# ver060_MCU.net
KiCad netlist of a schematic drawn in Altium Designer
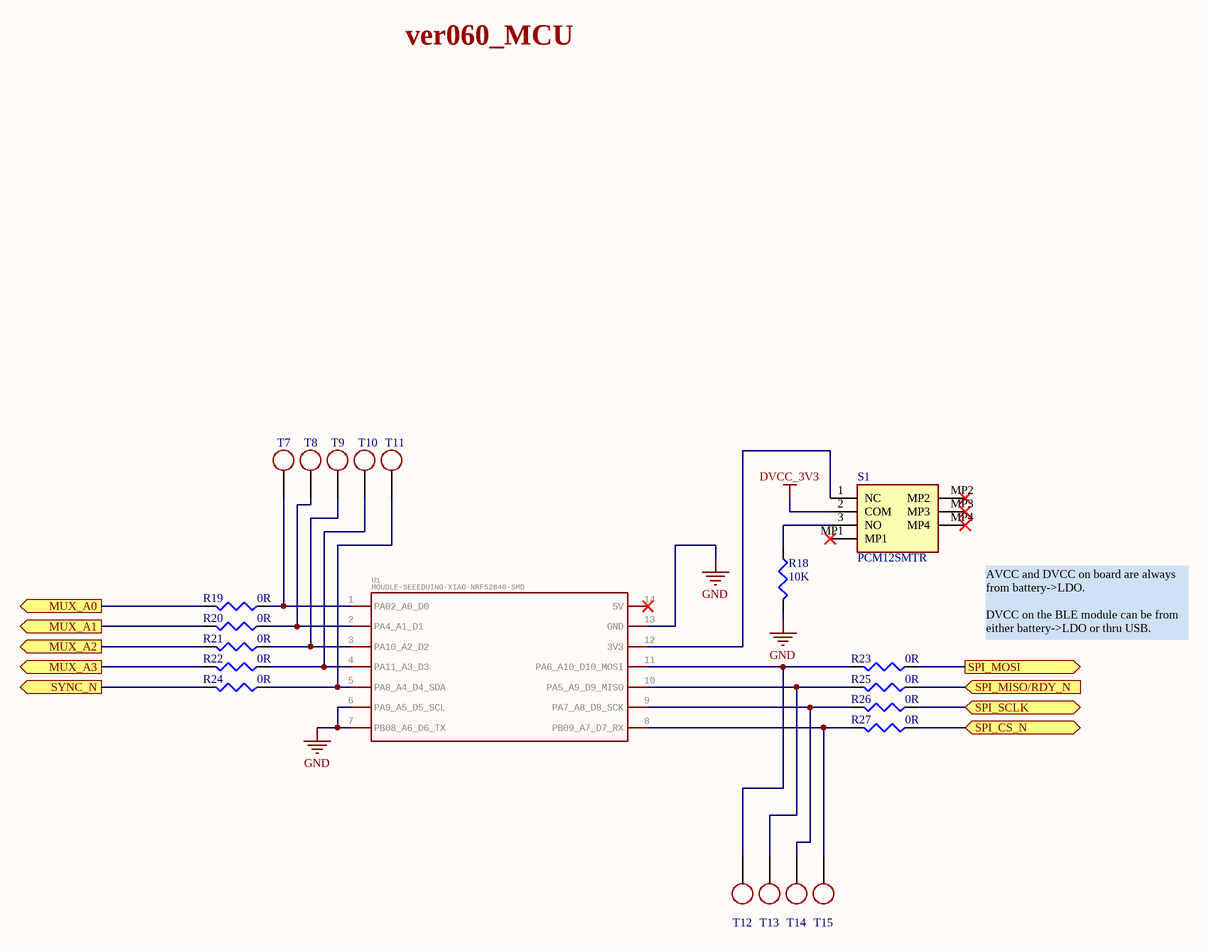
[diagram p0: ver060_MCU.SchDoc]

(export (version "E")
  (design (tool "Eeschema 10.0.6"))
  (components
    (comp (ref "R18")
      (value "10K")
      (footprint "J1-0603")
      (description "Resistor")
      (fields (field (name "Comment") "Res3") (field (name "PUBLISHER") "Altium Limited"))
      (libsource (lib "Miscellaneous Devices") (part "Res3"))
    )
    (comp (ref "R19")
      (value "0R")
      (footprint "J1-0603")
      (description "Resistor")
      (fields (field (name "Comment") "Res3") (field (name "PUBLISHER") "Altium Limited"))
      (libsource (lib "Miscellaneous Devices") (part "Res3"))
    )
    (comp (ref "R20")
      (value "0R")
      (footprint "J1-0603")
      (description "Resistor")
      (fields (field (name "Comment") "Res3") (field (name "PUBLISHER") "Altium Limited"))
      (libsource (lib "Miscellaneous Devices") (part "Res3"))
    )
    (comp (ref "R21")
      (value "0R")
      (footprint "J1-0603")
      (description "Resistor")
      (fields (field (name "Comment") "Res3") (field (name "PUBLISHER") "Altium Limited"))
      (libsource (lib "Miscellaneous Devices") (part "Res3"))
    )
    (comp (ref "R22")
      (value "0R")
      (footprint "J1-0603")
      (description "Resistor")
      (fields (field (name "Comment") "Res3") (field (name "PUBLISHER") "Altium Limited"))
      (libsource (lib "Miscellaneous Devices") (part "Res3"))
    )
    (comp (ref "R23")
      (value "0R")
      (footprint "J1-0603")
      (description "Resistor")
      (fields (field (name "Comment") "Res3") (field (name "PUBLISHER") "Altium Limited"))
      (libsource (lib "Miscellaneous Devices") (part "Res3"))
    )
    (comp (ref "R24")
      (value "0R")
      (footprint "J1-0603")
      (description "Resistor")
      (fields (field (name "Comment") "Res3") (field (name "PUBLISHER") "Altium Limited"))
      (libsource (lib "Miscellaneous Devices") (part "Res3"))
    )
    (comp (ref "R25")
      (value "0R")
      (footprint "J1-0603")
      (description "Resistor")
      (fields (field (name "Comment") "Res3") (field (name "PUBLISHER") "Altium Limited"))
      (libsource (lib "Miscellaneous Devices") (part "Res3"))
    )
    (comp (ref "R26")
      (value "0R")
      (footprint "J1-0603")
      (description "Resistor")
      (fields (field (name "Comment") "Res3") (field (name "PUBLISHER") "Altium Limited"))
      (libsource (lib "Miscellaneous Devices") (part "Res3"))
    )
    (comp (ref "R27")
      (value "0R")
      (footprint "J1-0603")
      (description "Resistor")
      (fields (field (name "Comment") "Res3") (field (name "PUBLISHER") "Altium Limited"))
      (libsource (lib "Miscellaneous Devices") (part "Res3"))
    )
    (comp (ref "S1")
      (value "PCM12SMTR")
      (footprint "nanowire:PCM12SMTR")
      (description "Switch")
      (fields (field (name "MOUSER PART NUMBER") "611-PCM12SMTR"))
      (libsource (lib "*") (part "PCM12SMTR"))
    )
    (comp (ref "T7")
      (value "TP_SMT")
      (footprint "TP_SMT_Round_0.6x0.6")
      (libsource (lib "nanowire") (part "TP_SMT"))
    )
    (comp (ref "T8")
      (value "TP_SMT")
      (footprint "TP_SMT_Round_0.6x0.6")
      (libsource (lib "nanowire") (part "TP_SMT"))
    )
    (comp (ref "T9")
      (value "TP_SMT")
      (footprint "TP_SMT_Round_0.6x0.6")
      (libsource (lib "nanowire") (part "TP_SMT"))
    )
    (comp (ref "T10")
      (value "TP_SMT")
      (footprint "TP_SMT_Round_0.6x0.6")
      (libsource (lib "nanowire") (part "TP_SMT"))
    )
    (comp (ref "T11")
      (value "TP_SMT")
      (footprint "TP_SMT_Round_0.6x0.6")
      (libsource (lib "nanowire") (part "TP_SMT"))
    )
    (comp (ref "T12")
      (value "TP_SMT")
      (footprint "TP_SMT_Round_0.6x0.6")
      (libsource (lib "nanowire") (part "TP_SMT"))
    )
    (comp (ref "T13")
      (value "TP_SMT")
      (footprint "TP_SMT_Round_0.6x0.6")
      (libsource (lib "nanowire") (part "TP_SMT"))
    )
    (comp (ref "T14")
      (value "TP_SMT")
      (footprint "TP_SMT_Round_0.6x0.6")
      (libsource (lib "nanowire") (part "TP_SMT"))
    )
    (comp (ref "T15")
      (value "TP_SMT")
      (footprint "TP_SMT_Round_0.6x0.6")
      (libsource (lib "nanowire") (part "TP_SMT"))
    )
    (comp (ref "U1")
      (value "MOUDLE-SEEEDUINO-XIAO-NRF52840-SMD")
      (footprint "MOUDLE16P-SMD-2-54-21X17-8MM")
      (fields (field (name "LIBRARYNAME") "Seeed-Studio-XIAO-nRF52840-footprint-eagle"))
      (libsource (lib "Seeed-Studio-XIAO-nRF52840-footprint-eagle") (part "MOUDLE-SEEEDUINO-XIAO-NRF52840-SMD"))
    )
  )
  (nets
    (net (code "1") (name "/MUX_A0") (class "Default")
      (node (ref "R19") (pin "2") (pinfunction "2_2") (pintype "passive"))
    )
    (net (code "2") (name "/MUX_A1") (class "Default")
      (node (ref "R20") (pin "2") (pinfunction "2_2") (pintype "passive"))
    )
    (net (code "3") (name "/MUX_A2") (class "Default")
      (node (ref "R21") (pin "2") (pinfunction "2_2") (pintype "passive"))
    )
    (net (code "4") (name "/MUX_A3") (class "Default")
      (node (ref "R22") (pin "2") (pinfunction "2_2") (pintype "passive"))
    )
    (net (code "5") (name "/SPI_CS_N") (class "Default")
      (node (ref "R27") (pin "1") (pinfunction "1_1") (pintype "passive"))
    )
    (net (code "6") (name "/SPI_MISO{slash}RDY_N") (class "Default")
      (node (ref "R25") (pin "1") (pinfunction "1_1") (pintype "passive"))
    )
    (net (code "7") (name "/SPI_MOSI") (class "Default")
      (node (ref "R23") (pin "1") (pinfunction "1_1") (pintype "passive"))
    )
    (net (code "8") (name "/SPI_SCLK") (class "Default")
      (node (ref "R26") (pin "1") (pinfunction "1_1") (pintype "passive"))
    )
    (net (code "9") (name "/SYNC_N") (class "Default")
      (node (ref "R24") (pin "2") (pinfunction "2_2") (pintype "passive"))
    )
    (net (code "10") (name "DVCC_3V3") (class "Default")
      (node (ref "S1") (pin "2") (pinfunction "COM_2") (pintype "passive"))
    )
    (net (code "11") (name "GND") (class "Default")
      (node (ref "R18") (pin "2") (pinfunction "2_2") (pintype "passive"))
      (node (ref "U1") (pin "13") (pinfunction "GND_13") (pintype "bidirectional"))
      (node (ref "U1") (pin "6") (pinfunction "PA9_A5_D5_SCL_6") (pintype "bidirectional"))
      (node (ref "U1") (pin "7") (pinfunction "PB08_A6_D6_TX_7") (pintype "bidirectional"))
    )
    (net (code "12") (name "Net-(S1-NC)") (class "Default")
      (node (ref "S1") (pin "1") (pinfunction "NC_1") (pintype "passive"))
      (node (ref "U1") (pin "12") (pinfunction "3V3_12") (pintype "bidirectional"))
    )
    (net (code "13") (name "Net-(S1-NO)") (class "Default")
      (node (ref "R18") (pin "1") (pinfunction "1_1") (pintype "passive"))
      (node (ref "S1") (pin "3") (pinfunction "NO_3") (pintype "passive"))
    )
    (net (code "14") (name "Net-(U1-PA02_A0_D0)") (class "Default")
      (node (ref "R19") (pin "1") (pinfunction "1_1") (pintype "passive"))
      (node (ref "T7") (pin "1") (pinfunction "1_1") (pintype "passive"))
      (node (ref "U1") (pin "1") (pinfunction "PA02_A0_D0_1") (pintype "bidirectional"))
    )
    (net (code "15") (name "Net-(U1-PA4_A1_D1)") (class "Default")
      (node (ref "R20") (pin "1") (pinfunction "1_1") (pintype "passive"))
      (node (ref "T8") (pin "1") (pinfunction "1_1") (pintype "passive"))
      (node (ref "U1") (pin "2") (pinfunction "PA4_A1_D1_2") (pintype "bidirectional"))
    )
    (net (code "16") (name "Net-(U1-PA5_A9_D9_MISO)") (class "Default")
      (node (ref "R25") (pin "2") (pinfunction "2_2") (pintype "passive"))
      (node (ref "T13") (pin "1") (pinfunction "1_1") (pintype "passive"))
      (node (ref "U1") (pin "10") (pinfunction "PA5_A9_D9_MISO_10") (pintype "bidirectional"))
    )
    (net (code "17") (name "Net-(U1-PA6_A10_D10_MOSI)") (class "Default")
      (node (ref "R23") (pin "2") (pinfunction "2_2") (pintype "passive"))
      (node (ref "T12") (pin "1") (pinfunction "1_1") (pintype "passive"))
      (node (ref "U1") (pin "11") (pinfunction "PA6_A10_D10_MOSI_11") (pintype "bidirectional"))
    )
    (net (code "18") (name "Net-(U1-PA7_A8_D8_SCK)") (class "Default")
      (node (ref "R26") (pin "2") (pinfunction "2_2") (pintype "passive"))
      (node (ref "T14") (pin "1") (pinfunction "1_1") (pintype "passive"))
      (node (ref "U1") (pin "9") (pinfunction "PA7_A8_D8_SCK_9") (pintype "bidirectional"))
    )
    (net (code "19") (name "Net-(U1-PA8_A4_D4_SDA)") (class "Default")
      (node (ref "R24") (pin "1") (pinfunction "1_1") (pintype "passive"))
      (node (ref "T11") (pin "1") (pinfunction "1_1") (pintype "passive"))
      (node (ref "U1") (pin "5") (pinfunction "PA8_A4_D4_SDA_5") (pintype "bidirectional"))
    )
    (net (code "20") (name "Net-(U1-PA10_A2_D2)") (class "Default")
      (node (ref "R21") (pin "1") (pinfunction "1_1") (pintype "passive"))
      (node (ref "T9") (pin "1") (pinfunction "1_1") (pintype "passive"))
      (node (ref "U1") (pin "3") (pinfunction "PA10_A2_D2_3") (pintype "bidirectional"))
    )
    (net (code "21") (name "Net-(U1-PA11_A3_D3)") (class "Default")
      (node (ref "R22") (pin "1") (pinfunction "1_1") (pintype "passive"))
      (node (ref "T10") (pin "1") (pinfunction "1_1") (pintype "passive"))
      (node (ref "U1") (pin "4") (pinfunction "PA11_A3_D3_4") (pintype "bidirectional"))
    )
    (net (code "22") (name "Net-(U1-PB09_A7_D7_RX)") (class "Default")
      (node (ref "R27") (pin "2") (pinfunction "2_2") (pintype "passive"))
      (node (ref "T15") (pin "1") (pinfunction "1_1") (pintype "passive"))
      (node (ref "U1") (pin "8") (pinfunction "PB09_A7_D7_RX_8") (pintype "bidirectional"))
    )
    (net (code "23") (name "unconnected-(S1-PadMP1)") (class "Default")
      (node (ref "S1") (pin "MP1") (pinfunction "MP1_MP1") (pintype "passive+no_connect"))
    )
    (net (code "24") (name "unconnected-(S1-PadMP2)") (class "Default")
      (node (ref "S1") (pin "MP2") (pinfunction "MP2_MP2") (pintype "passive+no_connect"))
    )
    (net (code "25") (name "unconnected-(S1-PadMP3)") (class "Default")
      (node (ref "S1") (pin "MP3") (pinfunction "MP3_MP3") (pintype "passive+no_connect"))
    )
    (net (code "26") (name "unconnected-(S1-PadMP4)") (class "Default")
      (node (ref "S1") (pin "MP4") (pinfunction "MP4_MP4") (pintype "passive+no_connect"))
    )
    (net (code "27") (name "unconnected-(U1-5V-Pad14)") (class "Default")
      (node (ref "U1") (pin "14") (pinfunction "5V_14") (pintype "bidirectional+no_connect"))
    )
  )
)
